# 3_STM32KIT_Power.net
KiCad netlist of a schematic drawn in Altium Designer
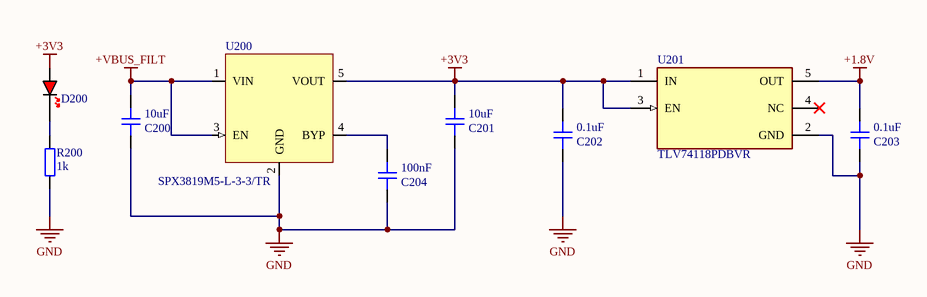
[diagram p0: 3_STM32KIT_Power.SchDoc]

(export (version "E")
  (design (tool "Eeschema 10.0.6"))
  (components
    (comp (ref "C200")
      (value "10uF")
      (footprint "CAP_0402")
      (description "Capacitor SMD 0402")
      (fields (field (name "SOURCE") "Schematic-Lib-PhilsLab.SchLib"))
      (libsource (lib "Industrial University of Ho Chi Minh City") (part "CAP_EL_NP_5MM"))
    )
    (comp (ref "C201")
      (value "10uF")
      (footprint "CAP_0402")
      (description "Capacitor SMD 0402")
      (fields (field (name "SOURCE") "Schematic-Lib-PhilsLab.SchLib"))
      (libsource (lib "Industrial University of Ho Chi Minh City") (part "CAP_EL_NP_5MM"))
    )
    (comp (ref "C202")
      (value "0.1uF")
      (footprint "CAP_0402")
      (description "Capacitor SMD 0402")
      (fields (field (name "SOURCE") "Schematic-Lib-PhilsLab.SchLib"))
      (libsource (lib "Industrial University of Ho Chi Minh City") (part "CAP_EL_NP_5MM"))
    )
    (comp (ref "C203")
      (value "0.1uF")
      (footprint "CAP_0402")
      (description "Capacitor SMD 0402")
      (fields (field (name "SOURCE") "Schematic-Lib-PhilsLab.SchLib"))
      (libsource (lib "Industrial University of Ho Chi Minh City") (part "CAP_EL_NP_5MM"))
    )
    (comp (ref "C204")
      (value "100nF")
      (footprint "CAP_0402")
      (description "Capacitor SMD 0402")
      (fields (field (name "SOURCE") "Schematic-Lib-PhilsLab.SchLib"))
      (libsource (lib "Industrial University of Ho Chi Minh City") (part "CAP_EL_NP_5MM"))
    )
    (comp (ref "D200")
      (value "RED")
      (footprint "LED_0402_RED")
      (description "LED 0402 RED SMD")
      (libsource (lib "Schematic-Lib-PhilsLab") (part "LED_0402_RED"))
    )
    (comp (ref "R200")
      (value "1k")
      (footprint "RES_0402")
      (description "Resistor SMD 0402")
      (libsource (lib "Schematic-Lib-PhilsLab") (part "RES_0402"))
    )
    (comp (ref "U200")
      (value "SPX3819M5-L-3-3/TR")
      (footprint "SOT-23-5")
      (description "500mA +3.3V Low-Noise LDO Voltage Regulator")
      (fields
        (field (name "MANUFACTURER") "MaxLinear")
        (field (name "SOURCE") "Schematic-Lib-PhilsLab.SchLib")
      )
      (libsource (lib "Industrial University of Ho Chi Minh City") (part "SPX3819M5-L-3-3/TR"))
    )
    (comp (ref "U201")
      (value "TLV74118PDBVR")
      (footprint "FP-DBV0005A-IPC_C")
      (description "None")
      (libsource (lib "Altium Content Vault") (part "843f007849b3ee74adb27ff62509038"))
    )
  )
  (nets
    (net (code "1") (name "+1.8V") (class "Default")
      (node (ref "C203") (pin "2") (pinfunction "2_2") (pintype "passive"))
      (node (ref "U201") (pin "5") (pinfunction "OUT_5") (pintype "power_in"))
    )
    (net (code "2") (name "+3V3") (class "Default")
      (node (ref "C201") (pin "2") (pinfunction "2_2") (pintype "passive"))
      (node (ref "C202") (pin "2") (pinfunction "2_2") (pintype "passive"))
      (node (ref "D200") (pin "A") (pinfunction "A_A") (pintype "passive"))
      (node (ref "U200") (pin "5") (pinfunction "VOUT_5") (pintype "power_in"))
      (node (ref "U201") (pin "1") (pinfunction "IN_1") (pintype "power_in"))
      (node (ref "U201") (pin "3") (pinfunction "EN_3") (pintype "input"))
    )
    (net (code "3") (name "+VBUS_FILT") (class "Default")
      (node (ref "C200") (pin "2") (pinfunction "2_2") (pintype "passive"))
      (node (ref "U200") (pin "1") (pinfunction "VIN_1") (pintype "power_in"))
      (node (ref "U200") (pin "3") (pinfunction "EN_3") (pintype "input"))
    )
    (net (code "4") (name "GND") (class "Default")
      (node (ref "C200") (pin "1") (pinfunction "1_1") (pintype "passive"))
      (node (ref "C201") (pin "1") (pinfunction "1_1") (pintype "passive"))
      (node (ref "C202") (pin "1") (pinfunction "1_1") (pintype "passive"))
      (node (ref "C203") (pin "1") (pinfunction "1_1") (pintype "passive"))
      (node (ref "C204") (pin "1") (pinfunction "1_1") (pintype "passive"))
      (node (ref "R200") (pin "1") (pinfunction "1_1") (pintype "passive"))
      (node (ref "U200") (pin "2") (pinfunction "GND_2") (pintype "power_in"))
      (node (ref "U201") (pin "2") (pinfunction "GND_2") (pintype "power_in"))
    )
    (net (code "5") (name "Net-(D200-PadK)") (class "Default")
      (node (ref "D200") (pin "K") (pinfunction "K_K") (pintype "passive"))
      (node (ref "R200") (pin "2") (pinfunction "2_2") (pintype "passive"))
    )
    (net (code "6") (name "Net-(U200-BYP)") (class "Default")
      (node (ref "C204") (pin "2") (pinfunction "2_2") (pintype "passive"))
      (node (ref "U200") (pin "4") (pinfunction "BYP_4") (pintype "passive"))
    )
    (net (code "7") (name "unconnected-(U201-NC-Pad4)") (class "Default")
      (node (ref "U201") (pin "4") (pinfunction "NC_4") (pintype "passive+no_connect"))
    )
  )
)
